# LED.net
KiCad netlist of a schematic drawn in Altium Designer
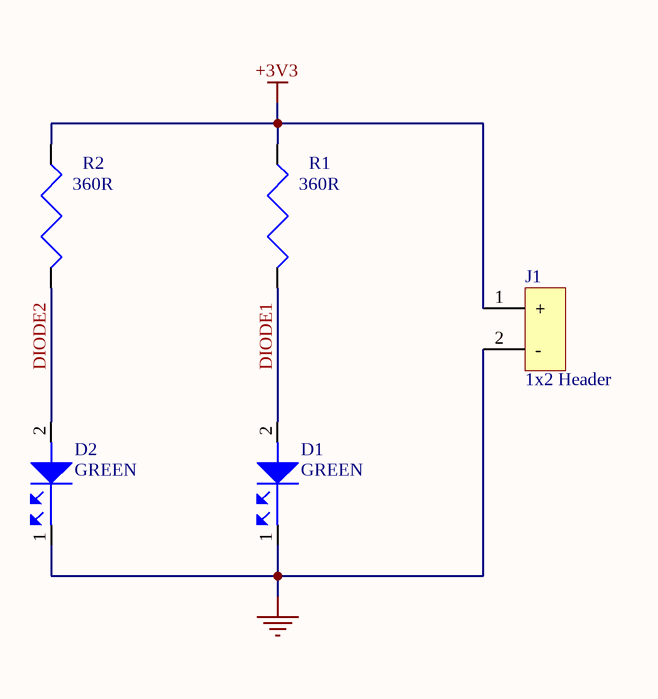
[diagram p0: LED.SchDoc]

(export (version "E")
  (design (tool "Eeschema 10.0.6"))
  (components
    (comp (ref "D1")
      (value "GREEN")
      (footprint "LED0603G")
      (description "LED GREEN CLEAR CHIP 0603 SMD")
      (fields
        (field (name "MANUFACTURER") "Visual Communications")
        (field (name "MANUFACTURER PART NUMBER") "LSM0603453V")
      )
      (libsource (lib "LED_Schlib") (part "LSM0603453V"))
    )
    (comp (ref "D2")
      (value "GREEN")
      (footprint "LED0603G")
      (description "LED GREEN CLEAR CHIP 0603 SMD")
      (fields
        (field (name "MANUFACTURER") "Visual Communications")
        (field (name "MANUFACTURER PART NUMBER") "LSM0603453V")
      )
      (libsource (lib "LED_Schlib") (part "LSM0603453V"))
    )
    (comp (ref "J1")
      (value "1x2 Header")
      (footprint "HDR1X2")
      (description "CONN HEADER VERT 2POS 2.54MM")
      (fields (field (name "MANUFACTURER") "Molex") (field (name "MANUFACTURER PART NUMBER") "22-27-2021"))
      (libsource (lib "LED_Schlib") (part "22-27-2021"))
    )
    (comp (ref "R1")
      (value "360R")
      (footprint "R0805")
      (description "RES 360 OHM 1% 1/8W 0805")
      (fields
        (field (name "MANUFACTURER") "Yageo")
        (field (name "MANUFACTURER PART NUMBER") "AC0805FR-10360RL")
      )
      (libsource (lib "LED_Schlib") (part "AC0805FR-10360RL"))
    )
    (comp (ref "R2")
      (value "360R")
      (footprint "R0805")
      (description "RES 360 OHM 1% 1/8W 0805")
      (fields
        (field (name "MANUFACTURER") "Yageo")
        (field (name "MANUFACTURER PART NUMBER") "AC0805FR-10360RL")
      )
      (libsource (lib "LED_Schlib") (part "AC0805FR-10360RL"))
    )
  )
  (nets
    (net (code "1") (name "+3V3") (class "Default")
      (node (ref "J1") (pin "1") (pinfunction "+_1") (pintype "passive"))
      (node (ref "R1") (pin "64") (pinfunction "64_64") (pintype "passive"))
      (node (ref "R2") (pin "64") (pinfunction "64_64") (pintype "passive"))
    )
    (net (code "2") (name "/DIODE1") (class "Default")
      (node (ref "D1") (pin "2") (pinfunction "66_2") (pintype "passive"))
    )
    (net (code "3") (name "/DIODE2") (class "Default")
      (node (ref "D2") (pin "2") (pinfunction "66_2") (pintype "passive"))
    )
    (net (code "4") (name "GND") (class "Default")
      (node (ref "D1") (pin "1") (pinfunction "65_1") (pintype "passive"))
      (node (ref "D2") (pin "1") (pinfunction "65_1") (pintype "passive"))
      (node (ref "J1") (pin "2") (pinfunction "-_2") (pintype "passive"))
    )
    (net (code "5") (name "unconnected-(R1-Pad65)") (class "Default")
      (node (ref "R1") (pin "65") (pinfunction "65_65") (pintype "passive"))
    )
    (net (code "6") (name "unconnected-(R2-Pad65)") (class "Default")
      (node (ref "R2") (pin "65") (pinfunction "65_65") (pintype "passive"))
    )
  )
)
